# esquematico3.net
KiCad netlist of a schematic drawn in EAGLE
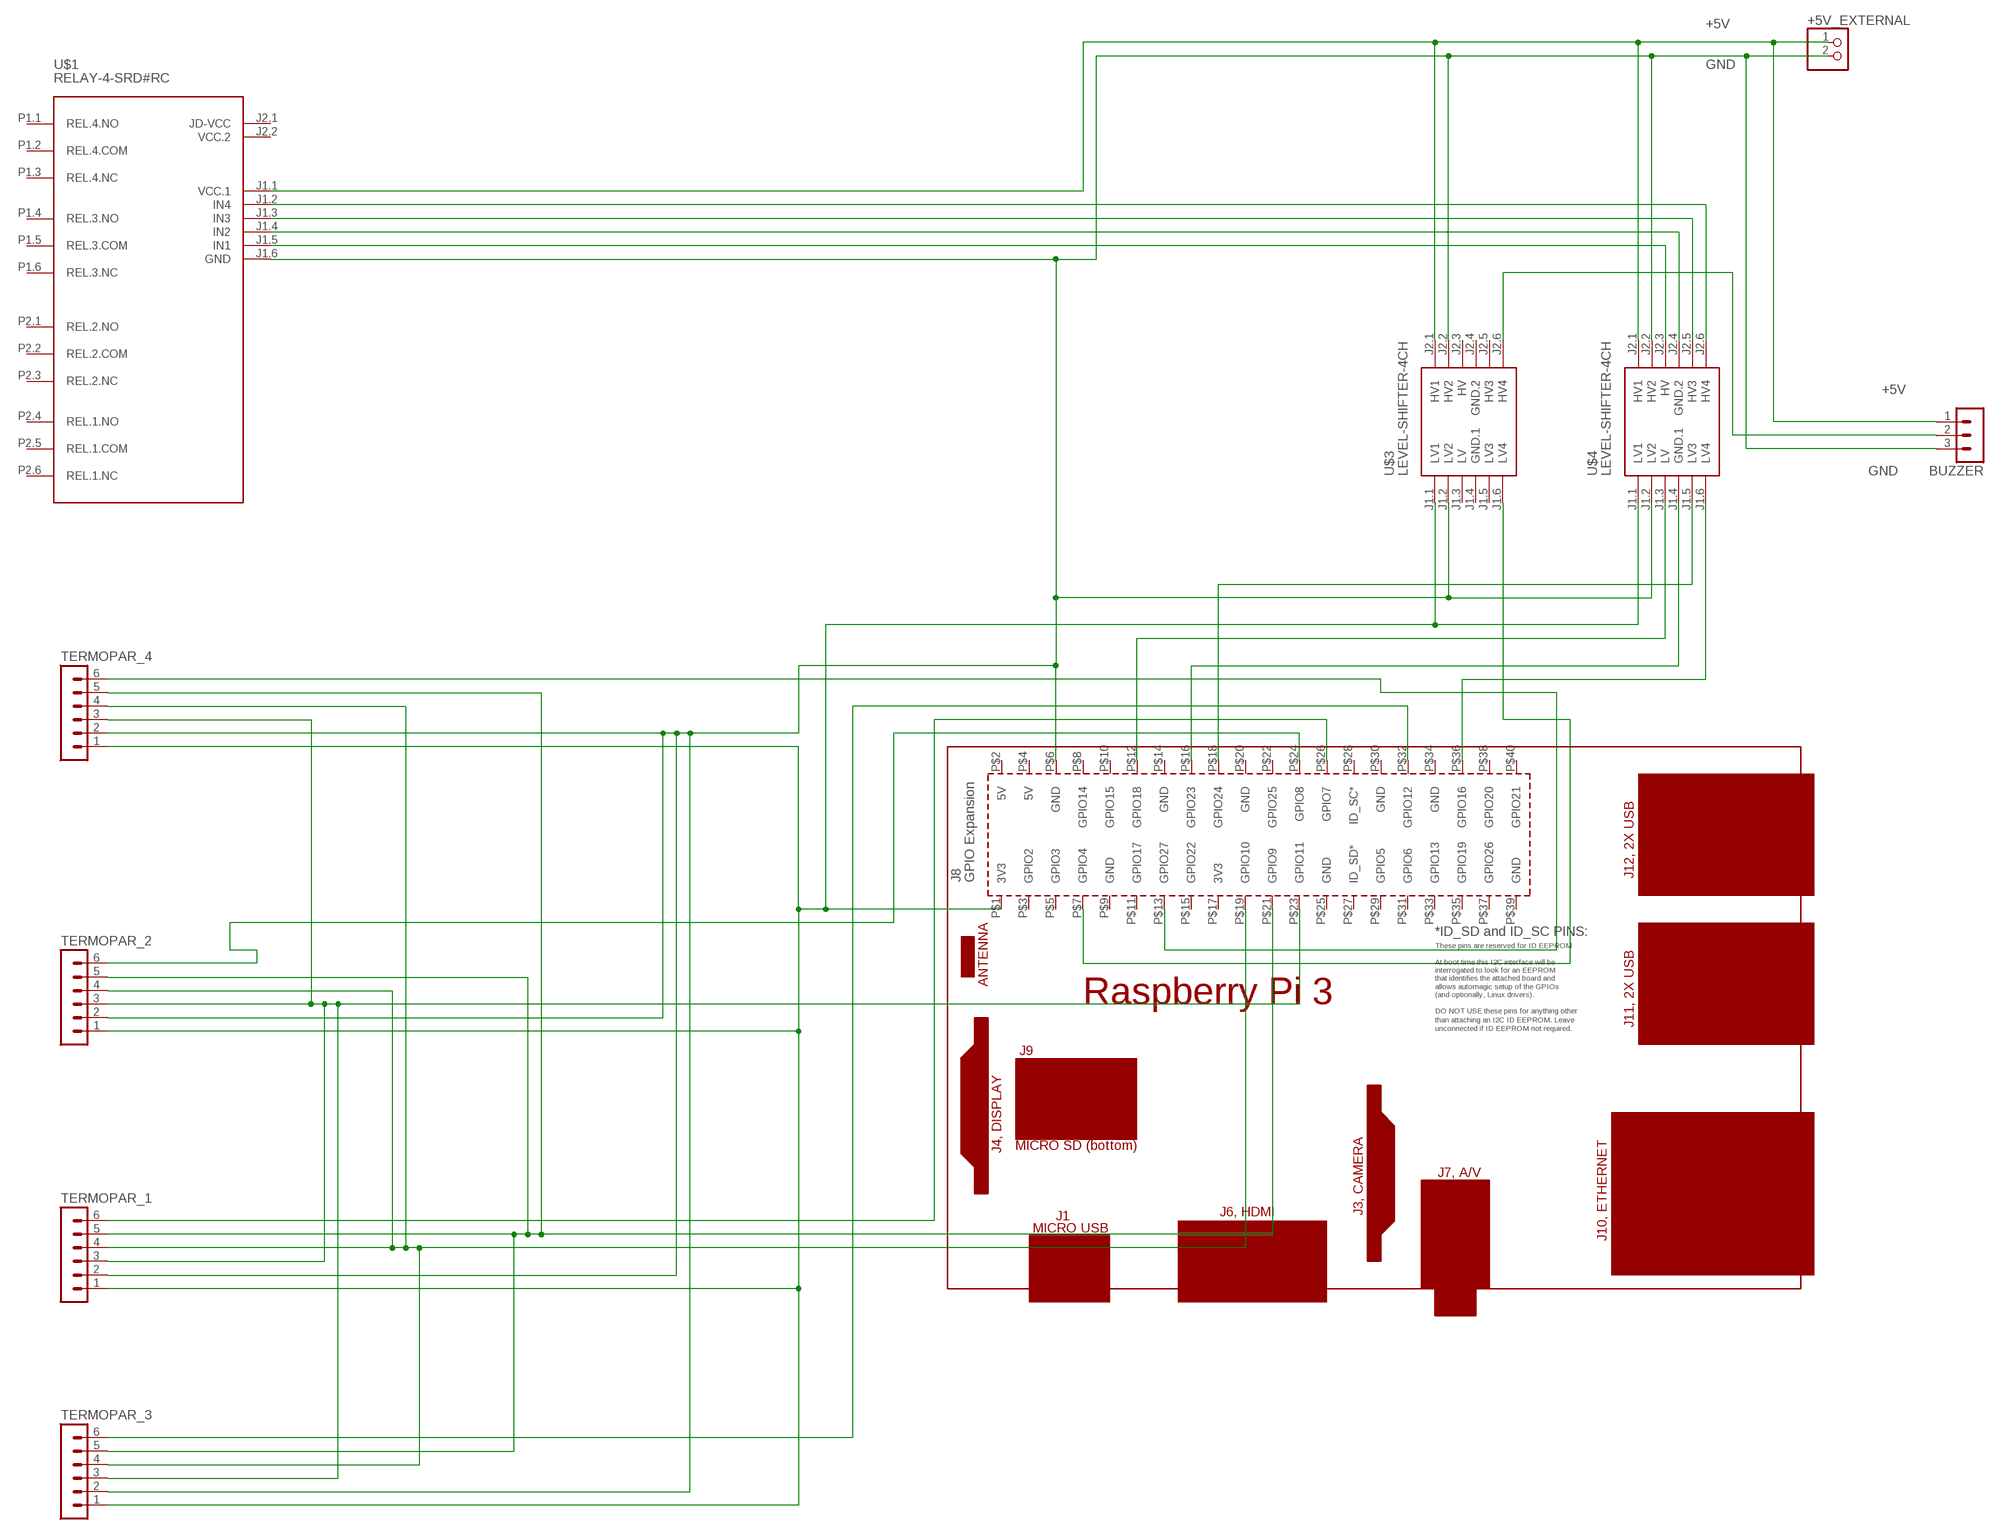
[diagram p0: schematic, sheet 1]

(export (version "E")
  (design (tool "Eeschema 10.0.6"))
  (components
    (comp (ref "+5V_EXTERNAL")
      (value "PINHD-1X2")
      (footprint "eagle-import:1X02")
      (libsource (lib "eagle-import") (part "PINHD-1X2"))
    )
    (comp (ref "BUZZER")
      (value "MA03-1")
      (footprint "eagle-import:MA03-1")
      (libsource (lib "eagle-import") (part "MA03-1"))
    )
    (comp (ref "PCB1")
      (value "RPI3RPI3")
      (footprint "eagle-import:RPI3")
      (libsource (lib "eagle-import") (part "RPI3RPI3"))
    )
    (comp (ref "TERMOPAR_1")
      (value "MA06-1")
      (footprint "eagle-import:MA06-1")
      (libsource (lib "eagle-import") (part "MA06-1"))
    )
    (comp (ref "TERMOPAR_2")
      (value "MA06-1")
      (footprint "eagle-import:MA06-1")
      (libsource (lib "eagle-import") (part "MA06-1"))
    )
    (comp (ref "TERMOPAR_3")
      (value "MA06-1")
      (footprint "eagle-import:MA06-1")
      (libsource (lib "eagle-import") (part "MA06-1"))
    )
    (comp (ref "TERMOPAR_4")
      (value "MA06-1")
      (footprint "eagle-import:MA06-1")
      (libsource (lib "eagle-import") (part "MA06-1"))
    )
    (comp (ref "U$1")
      (value "RELAY-4-SRD#RC")
      (footprint "eagle-import:RELAY-4-SRD#RC")
      (libsource (lib "eagle-import") (part "RELAY-4-SRD#RC"))
    )
    (comp (ref "U$3")
      (value "LEVEL-SHIFTER-4CH")
      (footprint "eagle-import:LEVEL-SHIFTER-4CH")
      (libsource (lib "eagle-import") (part "LEVEL-SHIFTER-4CH"))
    )
    (comp (ref "U$4")
      (value "LEVEL-SHIFTER-4CH")
      (footprint "eagle-import:LEVEL-SHIFTER-4CH")
      (libsource (lib "eagle-import") (part "LEVEL-SHIFTER-4CH"))
    )
  )
  (nets
    (net (code "1") (name "/+5V") (class "Default")
      (node (ref "+5V_EXTERNAL") (pin "1") (pinfunction "1_1") (pintype "passive"))
      (node (ref "BUZZER") (pin "1") (pinfunction "1_1") (pintype "passive"))
      (node (ref "U$1") (pin "J1.1") (pinfunction "VCC.1_J1.1") (pintype "power_in"))
      (node (ref "U$3") (pin "J2.1") (pinfunction "HV1_J2.1") (pintype "bidirectional"))
      (node (ref "U$4") (pin "J2.1") (pinfunction "HV1_J2.1") (pintype "bidirectional"))
    )
    (net (code "2") (name "/GND") (class "Default")
      (node (ref "+5V_EXTERNAL") (pin "2") (pinfunction "2_2") (pintype "passive"))
      (node (ref "BUZZER") (pin "3") (pinfunction "3_3") (pintype "passive"))
      (node (ref "PCB1") (pin "P$6") (pinfunction "GND_P$6") (pintype "bidirectional"))
      (node (ref "TERMOPAR_1") (pin "2") (pinfunction "2_2") (pintype "passive"))
      (node (ref "TERMOPAR_2") (pin "2") (pinfunction "2_2") (pintype "passive"))
      (node (ref "TERMOPAR_3") (pin "2") (pinfunction "2_2") (pintype "passive"))
      (node (ref "TERMOPAR_4") (pin "2") (pinfunction "2_2") (pintype "passive"))
      (node (ref "U$1") (pin "J1.6") (pinfunction "GND_J1.6") (pintype "power_in"))
      (node (ref "U$3") (pin "J1.2") (pinfunction "LV2_J1.2") (pintype "bidirectional"))
      (node (ref "U$3") (pin "J2.2") (pinfunction "HV2_J2.2") (pintype "bidirectional"))
      (node (ref "U$4") (pin "J1.2") (pinfunction "LV2_J1.2") (pintype "bidirectional"))
      (node (ref "U$4") (pin "J2.2") (pinfunction "HV2_J2.2") (pintype "bidirectional"))
    )
    (net (code "3") (name "/GND.1") (class "Default")
      (node (ref "U$3") (pin "J1.4") (pinfunction "GND.1_J1.4") (pintype "power_in"))
    )
    (net (code "4") (name "/GND.2") (class "Default")
      (node (ref "U$3") (pin "J2.4") (pinfunction "GND.2_J2.4") (pintype "power_in"))
    )
    (net (code "5") (name "/HV") (class "Default")
      (node (ref "U$3") (pin "J2.3") (pinfunction "HV_J2.3") (pintype "power_in"))
    )
    (net (code "6") (name "/LV") (class "Default")
      (node (ref "U$3") (pin "J1.3") (pinfunction "LV_J1.3") (pintype "power_in"))
    )
    (net (code "7") (name "Net-(PCB1-GPIO4)") (class "Default")
      (node (ref "PCB1") (pin "P$7") (pinfunction "GPIO4_P$7") (pintype "bidirectional"))
      (node (ref "U$3") (pin "J1.6") (pinfunction "LV4_J1.6") (pintype "bidirectional"))
    )
    (net (code "8") (name "Net-(PCB1-GPIO7)") (class "Default")
      (node (ref "PCB1") (pin "P$26") (pinfunction "GPIO7_P$26") (pintype "bidirectional"))
      (node (ref "TERMOPAR_1") (pin "6") (pinfunction "6_6") (pintype "passive"))
    )
    (net (code "9") (name "Net-(PCB1-GPIO8)") (class "Default")
      (node (ref "PCB1") (pin "P$24") (pinfunction "GPIO8_P$24") (pintype "bidirectional"))
      (node (ref "TERMOPAR_2") (pin "6") (pinfunction "6_6") (pintype "passive"))
    )
    (net (code "10") (name "Net-(PCB1-GPIO9)") (class "Default")
      (node (ref "PCB1") (pin "P$21") (pinfunction "GPIO9_P$21") (pintype "bidirectional"))
      (node (ref "TERMOPAR_1") (pin "5") (pinfunction "5_5") (pintype "passive"))
      (node (ref "TERMOPAR_2") (pin "5") (pinfunction "5_5") (pintype "passive"))
      (node (ref "TERMOPAR_3") (pin "5") (pinfunction "5_5") (pintype "passive"))
      (node (ref "TERMOPAR_4") (pin "5") (pinfunction "5_5") (pintype "passive"))
    )
    (net (code "11") (name "Net-(PCB1-GPIO10)") (class "Default")
      (node (ref "PCB1") (pin "P$19") (pinfunction "GPIO10_P$19") (pintype "bidirectional"))
      (node (ref "TERMOPAR_1") (pin "4") (pinfunction "4_4") (pintype "passive"))
      (node (ref "TERMOPAR_2") (pin "4") (pinfunction "4_4") (pintype "passive"))
      (node (ref "TERMOPAR_3") (pin "4") (pinfunction "4_4") (pintype "passive"))
      (node (ref "TERMOPAR_4") (pin "4") (pinfunction "4_4") (pintype "passive"))
    )
    (net (code "12") (name "Net-(PCB1-GPIO11)") (class "Default")
      (node (ref "PCB1") (pin "P$23") (pinfunction "GPIO11_P$23") (pintype "bidirectional"))
      (node (ref "TERMOPAR_1") (pin "3") (pinfunction "3_3") (pintype "passive"))
      (node (ref "TERMOPAR_2") (pin "3") (pinfunction "3_3") (pintype "passive"))
      (node (ref "TERMOPAR_3") (pin "3") (pinfunction "3_3") (pintype "passive"))
      (node (ref "TERMOPAR_4") (pin "3") (pinfunction "3_3") (pintype "passive"))
    )
    (net (code "13") (name "Net-(PCB1-GPIO12)") (class "Default")
      (node (ref "PCB1") (pin "P$32") (pinfunction "GPIO12_P$32") (pintype "bidirectional"))
      (node (ref "TERMOPAR_3") (pin "6") (pinfunction "6_6") (pintype "passive"))
    )
    (net (code "14") (name "Net-(PCB1-GPIO16)") (class "Default")
      (node (ref "PCB1") (pin "P$36") (pinfunction "GPIO16_P$36") (pintype "bidirectional"))
      (node (ref "U$4") (pin "J1.6") (pinfunction "LV4_J1.6") (pintype "bidirectional"))
    )
    (net (code "15") (name "Net-(PCB1-GPIO18)") (class "Default")
      (node (ref "PCB1") (pin "P$12") (pinfunction "GPIO18_P$12") (pintype "bidirectional"))
      (node (ref "U$4") (pin "J1.3") (pinfunction "LV_J1.3") (pintype "power_in"))
    )
    (net (code "16") (name "Net-(PCB1-GPIO23)") (class "Default")
      (node (ref "PCB1") (pin "P$16") (pinfunction "GPIO23_P$16") (pintype "bidirectional"))
      (node (ref "U$4") (pin "J1.4") (pinfunction "GND.1_J1.4") (pintype "power_in"))
    )
    (net (code "17") (name "Net-(PCB1-GPIO24)") (class "Default")
      (node (ref "PCB1") (pin "P$18") (pinfunction "GPIO24_P$18") (pintype "bidirectional"))
      (node (ref "U$4") (pin "J1.5") (pinfunction "LV3_J1.5") (pintype "bidirectional"))
    )
    (net (code "18") (name "Net-(PCB1-GPIO27)") (class "Default")
      (node (ref "PCB1") (pin "P$13") (pinfunction "GPIO27_P$13") (pintype "bidirectional"))
      (node (ref "TERMOPAR_4") (pin "6") (pinfunction "6_6") (pintype "passive"))
    )
    (net (code "19") (name "Net-(U$1-IN1)") (class "Default")
      (node (ref "U$1") (pin "J1.5") (pinfunction "IN1_J1.5") (pintype "bidirectional"))
      (node (ref "U$4") (pin "J2.3") (pinfunction "HV_J2.3") (pintype "power_in"))
    )
    (net (code "20") (name "Net-(U$1-IN2)") (class "Default")
      (node (ref "U$1") (pin "J1.4") (pinfunction "IN2_J1.4") (pintype "bidirectional"))
      (node (ref "U$4") (pin "J2.4") (pinfunction "GND.2_J2.4") (pintype "power_in"))
    )
    (net (code "21") (name "Net-(U$1-IN3)") (class "Default")
      (node (ref "U$1") (pin "J1.3") (pinfunction "IN3_J1.3") (pintype "bidirectional"))
      (node (ref "U$4") (pin "J2.5") (pinfunction "HV3_J2.5") (pintype "bidirectional"))
    )
    (net (code "22") (name "Net-(U$1-IN4)") (class "Default")
      (node (ref "U$1") (pin "J1.2") (pinfunction "IN4_J1.2") (pintype "bidirectional"))
      (node (ref "U$4") (pin "J2.6") (pinfunction "HV4_J2.6") (pintype "bidirectional"))
    )
    (net (code "23") (name "Net-(U$3-HV4)") (class "Default")
      (node (ref "BUZZER") (pin "2") (pinfunction "2_2") (pintype "passive"))
      (node (ref "U$3") (pin "J2.6") (pinfunction "HV4_J2.6") (pintype "bidirectional"))
    )
    (net (code "24") (name "Net-(U$3-LV1)") (class "Default")
      (node (ref "PCB1") (pin "P$1") (pinfunction "3V3_P$1") (pintype "bidirectional"))
      (node (ref "TERMOPAR_1") (pin "1") (pinfunction "1_1") (pintype "passive"))
      (node (ref "TERMOPAR_2") (pin "1") (pinfunction "1_1") (pintype "passive"))
      (node (ref "TERMOPAR_3") (pin "1") (pinfunction "1_1") (pintype "passive"))
      (node (ref "TERMOPAR_4") (pin "1") (pinfunction "1_1") (pintype "passive"))
      (node (ref "U$3") (pin "J1.1") (pinfunction "LV1_J1.1") (pintype "bidirectional"))
      (node (ref "U$4") (pin "J1.1") (pinfunction "LV1_J1.1") (pintype "bidirectional"))
    )
    (net (code "25") (name "unconnected-(PCB1-3V3-PadP$17)") (class "Default")
      (node (ref "PCB1") (pin "P$17") (pinfunction "3V3_P$17") (pintype "bidirectional"))
    )
    (net (code "26") (name "unconnected-(PCB1-5V-PadP$2)") (class "Default")
      (node (ref "PCB1") (pin "P$2") (pinfunction "5V_P$2") (pintype "bidirectional"))
    )
    (net (code "27") (name "unconnected-(PCB1-5V-PadP$4)") (class "Default")
      (node (ref "PCB1") (pin "P$4") (pinfunction "5V_P$4") (pintype "bidirectional"))
    )
    (net (code "28") (name "unconnected-(PCB1-GND-PadP$9)") (class "Default")
      (node (ref "PCB1") (pin "P$9") (pinfunction "GND_P$9") (pintype "bidirectional"))
    )
    (net (code "29") (name "unconnected-(PCB1-GND-PadP$14)") (class "Default")
      (node (ref "PCB1") (pin "P$14") (pinfunction "GND_P$14") (pintype "bidirectional"))
    )
    (net (code "30") (name "unconnected-(PCB1-GND-PadP$20)") (class "Default")
      (node (ref "PCB1") (pin "P$20") (pinfunction "GND_P$20") (pintype "bidirectional"))
    )
    (net (code "31") (name "unconnected-(PCB1-GND-PadP$25)") (class "Default")
      (node (ref "PCB1") (pin "P$25") (pinfunction "GND_P$25") (pintype "bidirectional"))
    )
    (net (code "32") (name "unconnected-(PCB1-GND-PadP$30)") (class "Default")
      (node (ref "PCB1") (pin "P$30") (pinfunction "GND_P$30") (pintype "bidirectional"))
    )
    (net (code "33") (name "unconnected-(PCB1-GND-PadP$34)") (class "Default")
      (node (ref "PCB1") (pin "P$34") (pinfunction "GND_P$34") (pintype "bidirectional"))
    )
    (net (code "34") (name "unconnected-(PCB1-GND-PadP$39)") (class "Default")
      (node (ref "PCB1") (pin "P$39") (pinfunction "GND_P$39") (pintype "bidirectional"))
    )
    (net (code "35") (name "unconnected-(PCB1-GPIO2-PadP$3)") (class "Default")
      (node (ref "PCB1") (pin "P$3") (pinfunction "GPIO2_P$3") (pintype "bidirectional"))
    )
    (net (code "36") (name "unconnected-(PCB1-GPIO3-PadP$5)") (class "Default")
      (node (ref "PCB1") (pin "P$5") (pinfunction "GPIO3_P$5") (pintype "bidirectional"))
    )
    (net (code "37") (name "unconnected-(PCB1-GPIO5-PadP$29)") (class "Default")
      (node (ref "PCB1") (pin "P$29") (pinfunction "GPIO5_P$29") (pintype "bidirectional"))
    )
    (net (code "38") (name "unconnected-(PCB1-GPIO6-PadP$31)") (class "Default")
      (node (ref "PCB1") (pin "P$31") (pinfunction "GPIO6_P$31") (pintype "bidirectional"))
    )
    (net (code "39") (name "unconnected-(PCB1-GPIO13-PadP$33)") (class "Default")
      (node (ref "PCB1") (pin "P$33") (pinfunction "GPIO13_P$33") (pintype "bidirectional"))
    )
    (net (code "40") (name "unconnected-(PCB1-GPIO14-PadP$8)") (class "Default")
      (node (ref "PCB1") (pin "P$8") (pinfunction "GPIO14_P$8") (pintype "bidirectional"))
    )
    (net (code "41") (name "unconnected-(PCB1-GPIO15-PadP$10)") (class "Default")
      (node (ref "PCB1") (pin "P$10") (pinfunction "GPIO15_P$10") (pintype "bidirectional"))
    )
    (net (code "42") (name "unconnected-(PCB1-GPIO17-PadP$11)") (class "Default")
      (node (ref "PCB1") (pin "P$11") (pinfunction "GPIO17_P$11") (pintype "bidirectional"))
    )
    (net (code "43") (name "unconnected-(PCB1-GPIO19-PadP$35)") (class "Default")
      (node (ref "PCB1") (pin "P$35") (pinfunction "GPIO19_P$35") (pintype "bidirectional"))
    )
    (net (code "44") (name "unconnected-(PCB1-GPIO20-PadP$38)") (class "Default")
      (node (ref "PCB1") (pin "P$38") (pinfunction "GPIO20_P$38") (pintype "bidirectional"))
    )
    (net (code "45") (name "unconnected-(PCB1-GPIO21-PadP$40)") (class "Default")
      (node (ref "PCB1") (pin "P$40") (pinfunction "GPIO21_P$40") (pintype "bidirectional"))
    )
    (net (code "46") (name "unconnected-(PCB1-GPIO22-PadP$15)") (class "Default")
      (node (ref "PCB1") (pin "P$15") (pinfunction "GPIO22_P$15") (pintype "bidirectional"))
    )
    (net (code "47") (name "unconnected-(PCB1-GPIO25-PadP$22)") (class "Default")
      (node (ref "PCB1") (pin "P$22") (pinfunction "GPIO25_P$22") (pintype "bidirectional"))
    )
    (net (code "48") (name "unconnected-(PCB1-GPIO26-PadP$37)") (class "Default")
      (node (ref "PCB1") (pin "P$37") (pinfunction "GPIO26_P$37") (pintype "bidirectional"))
    )
    (net (code "49") (name "unconnected-(PCB1-ID_SC*-PadP$28)") (class "Default")
      (node (ref "PCB1") (pin "P$28") (pinfunction "ID_SC*_P$28") (pintype "bidirectional"))
    )
    (net (code "50") (name "unconnected-(PCB1-ID_SD*-PadP$27)") (class "Default")
      (node (ref "PCB1") (pin "P$27") (pinfunction "ID_SD*_P$27") (pintype "bidirectional"))
    )
    (net (code "51") (name "unconnected-(U$1-JD-VCC-PadJ2.1)") (class "Default")
      (node (ref "U$1") (pin "J2.1") (pinfunction "JD-VCC_J2.1") (pintype "bidirectional"))
    )
    (net (code "52") (name "unconnected-(U$1-REL.1.COM-PadP2.5)") (class "Default")
      (node (ref "U$1") (pin "P2.5") (pinfunction "REL.1.COM_P2.5") (pintype "bidirectional"))
    )
    (net (code "53") (name "unconnected-(U$1-REL.1.NC-PadP2.6)") (class "Default")
      (node (ref "U$1") (pin "P2.6") (pinfunction "REL.1.NC_P2.6") (pintype "bidirectional"))
    )
    (net (code "54") (name "unconnected-(U$1-REL.1.NO-PadP2.4)") (class "Default")
      (node (ref "U$1") (pin "P2.4") (pinfunction "REL.1.NO_P2.4") (pintype "bidirectional"))
    )
    (net (code "55") (name "unconnected-(U$1-REL.2.COM-PadP2.2)") (class "Default")
      (node (ref "U$1") (pin "P2.2") (pinfunction "REL.2.COM_P2.2") (pintype "bidirectional"))
    )
    (net (code "56") (name "unconnected-(U$1-REL.2.NC-PadP2.3)") (class "Default")
      (node (ref "U$1") (pin "P2.3") (pinfunction "REL.2.NC_P2.3") (pintype "bidirectional"))
    )
    (net (code "57") (name "unconnected-(U$1-REL.2.NO-PadP2.1)") (class "Default")
      (node (ref "U$1") (pin "P2.1") (pinfunction "REL.2.NO_P2.1") (pintype "bidirectional"))
    )
    (net (code "58") (name "unconnected-(U$1-REL.3.COM-PadP1.5)") (class "Default")
      (node (ref "U$1") (pin "P1.5") (pinfunction "REL.3.COM_P1.5") (pintype "bidirectional"))
    )
    (net (code "59") (name "unconnected-(U$1-REL.3.NC-PadP1.6)") (class "Default")
      (node (ref "U$1") (pin "P1.6") (pinfunction "REL.3.NC_P1.6") (pintype "bidirectional"))
    )
    (net (code "60") (name "unconnected-(U$1-REL.3.NO-PadP1.4)") (class "Default")
      (node (ref "U$1") (pin "P1.4") (pinfunction "REL.3.NO_P1.4") (pintype "bidirectional"))
    )
    (net (code "61") (name "unconnected-(U$1-REL.4.COM-PadP1.2)") (class "Default")
      (node (ref "U$1") (pin "P1.2") (pinfunction "REL.4.COM_P1.2") (pintype "bidirectional"))
    )
    (net (code "62") (name "unconnected-(U$1-REL.4.NC-PadP1.3)") (class "Default")
      (node (ref "U$1") (pin "P1.3") (pinfunction "REL.4.NC_P1.3") (pintype "bidirectional"))
    )
    (net (code "63") (name "unconnected-(U$1-REL.4.NO-PadP1.1)") (class "Default")
      (node (ref "U$1") (pin "P1.1") (pinfunction "REL.4.NO_P1.1") (pintype "bidirectional"))
    )
    (net (code "64") (name "unconnected-(U$1-VCC.2-PadJ2.2)") (class "Default")
      (node (ref "U$1") (pin "J2.2") (pinfunction "VCC.2_J2.2") (pintype "power_in"))
    )
    (net (code "65") (name "unconnected-(U$3-HV3-PadJ2.5)") (class "Default")
      (node (ref "U$3") (pin "J2.5") (pinfunction "HV3_J2.5") (pintype "bidirectional"))
    )
    (net (code "66") (name "unconnected-(U$3-LV3-PadJ1.5)") (class "Default")
      (node (ref "U$3") (pin "J1.5") (pinfunction "LV3_J1.5") (pintype "bidirectional"))
    )
  )
)
